# 5V_Output_shift.net
KiCad netlist of a schematic drawn in Altium Designer
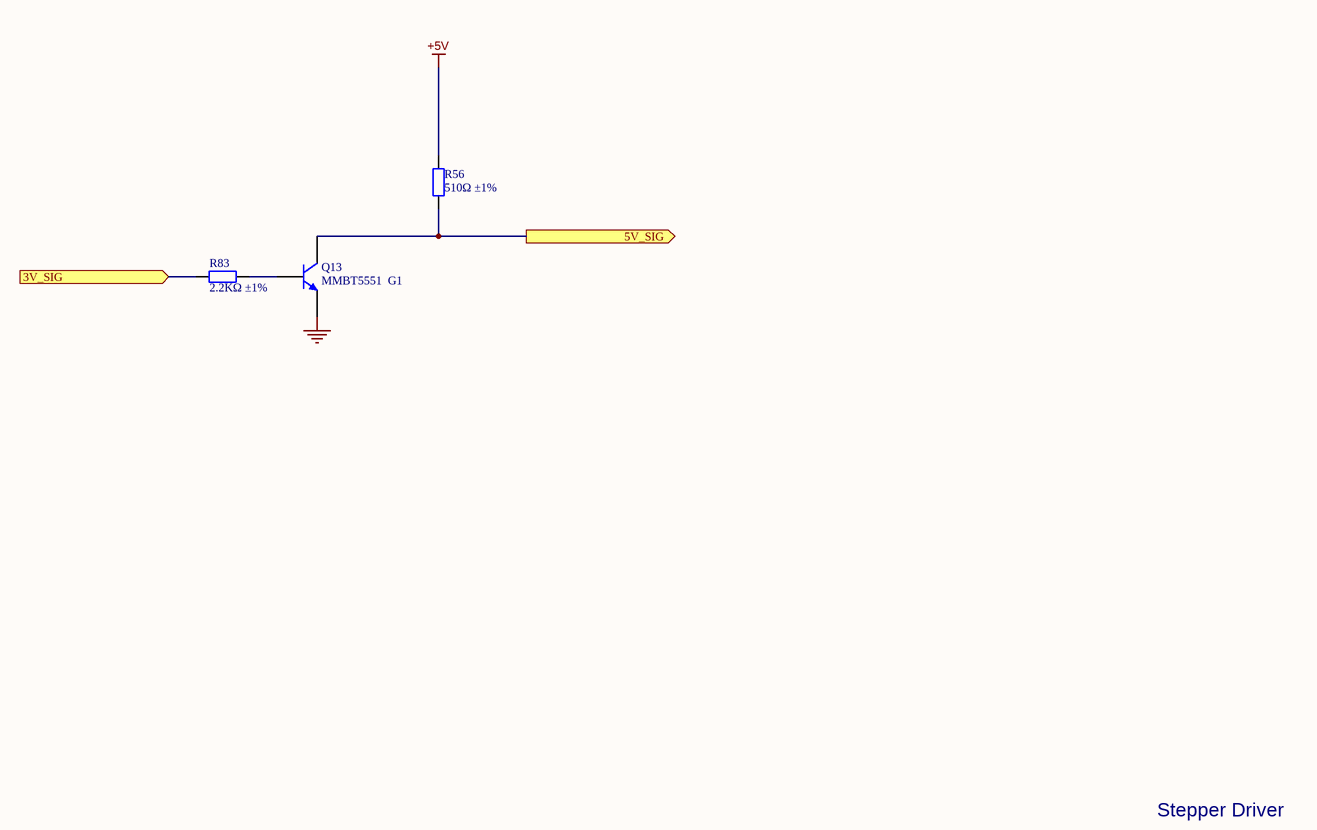
[diagram p0: 5V_Output_shift.SchDoc]

(export (version "E")
  (design (tool "Eeschema 10.0.6"))
  (components
    (comp (ref "Q13")
      (value "MMBT5551  G1")
      (footprint "SOT-23(SOT-23-3)")
      (description "三极管")
      (libsource (lib "Transistor_NPN") (part "SOT-23 MMBT5551  G1"))
    )
    (comp (ref "R56")
      (value "510Ω ±1%")
      (footprint "0402_R")
      (description "Chip resistor")
      (fields (field (name "MANUFACTURER") "Uniroyal Elec") (field (name "PARTNUMBER") "0402WGF5100TCE"))
      (libsource (lib "RES") (part "0402 510R (5100) 1%"))
    )
    (comp (ref "R83")
      (value "2.2KΩ ±1%")
      (footprint "0402_R")
      (description "Chip resistor")
      (fields (field (name "MANUFACTURER") "Uniroyal Elec") (field (name "PARTNUMBER") "0402WGF2201TCE"))
      (libsource (lib "RES") (part "0402 2.2K (2201) 1%"))
    )
  )
  (nets
    (net (code "1") (name "+5V") (class "Default")
      (node (ref "R56") (pin "2") (pinfunction "2_2") (pintype "passive"))
    )
    (net (code "2") (name "/3V_SIG") (class "Default")
      (node (ref "R83") (pin "1") (pinfunction "1_1") (pintype "passive"))
    )
    (net (code "3") (name "/5V_SIG") (class "Default")
      (node (ref "Q13") (pin "3") (pinfunction "C_3") (pintype "passive"))
      (node (ref "R56") (pin "1") (pinfunction "1_1") (pintype "passive"))
    )
    (net (code "4") (name "GND") (class "Default")
      (node (ref "Q13") (pin "2") (pinfunction "E_2") (pintype "passive"))
    )
    (net (code "5") (name "Net-(Q13-B)") (class "Default")
      (node (ref "Q13") (pin "1") (pinfunction "B_1") (pintype "passive"))
      (node (ref "R83") (pin "2") (pinfunction "2_2") (pintype "passive"))
    )
  )
)
